# 18_ETH.net
KiCad netlist of a schematic drawn in Altium Designer
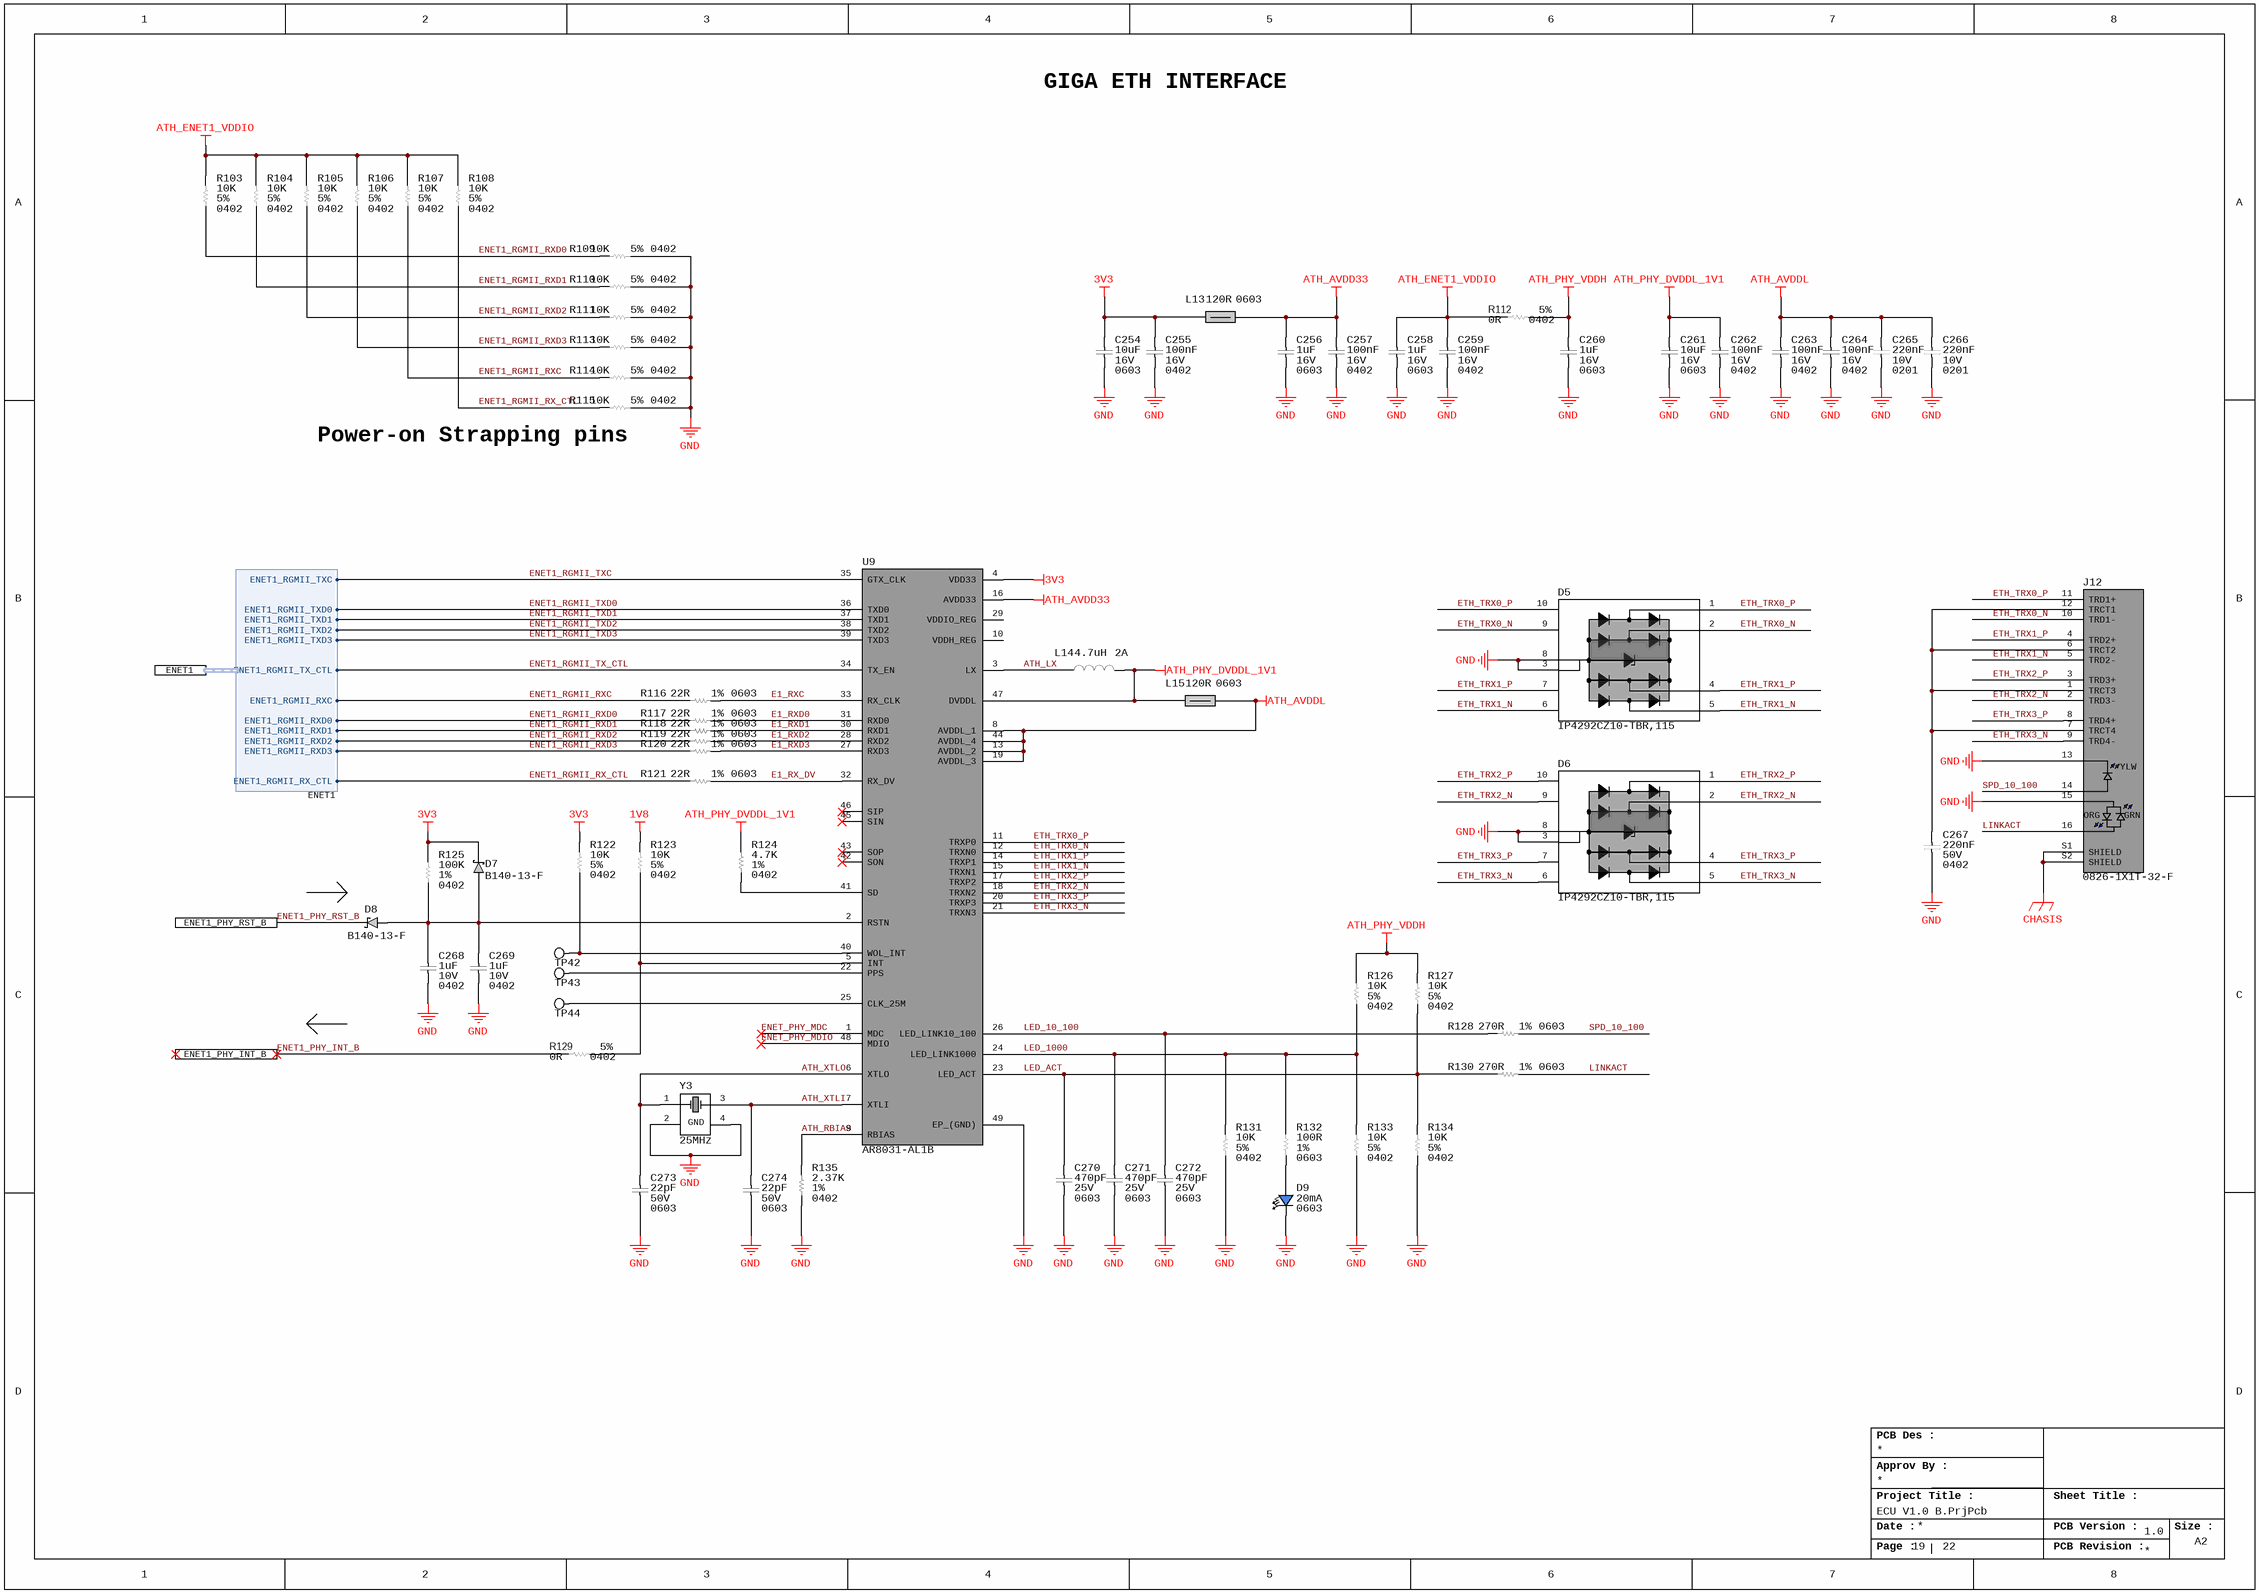
[diagram p0: 18_ETH.SchDoc]

(export (version "E")
  (design (tool "Eeschema 10.0.6"))
  (components
    (comp (ref "C254")
      (value "GRM188R61C106MAALD")
      (footprint "CAP_0603_CAPC1608X08N")
      (description "0603 10 uF 16 V ±20% Tolerance X5R Multilayer Ceramic Chip Capacitor")
      (fields
        (field (name "MANUFACTURER") "Murata")
        (field (name "TOLERANCE") "20%")
        (field (name "VOLTAGE RATING") "16V")
        (field (name "CAPACITANCE") "10uF")
        (field (name "CASE/PACKAGE") "0603")
      )
      (libsource (lib "Electronic Devices_LIB") (part "CAP_10UF_16V_X5R_0603"))
    )
    (comp (ref "C255")
      (value "CL05B104KO5NNNC")
      (footprint "CAP_0402_CAPC1005X05N")
      (description "Multilayer Ceramic Capacitor, 0.1 uF, 16 V, ± 10%, X7R, 0402 [1005 Metric]")
      (fields
        (field (name "MANUFACTURER") "Samsung")
        (field (name "TOLERANCE") "10%")
        (field (name "VOLTAGE RATING") "16V")
        (field (name "CAPACITANCE") "100nF")
        (field (name "CASE/PACKAGE") "0402")
      )
      (libsource (lib "Electronic Devices_LIB") (part "CAP_100NF_16V_X7R_0402"))
    )
    (comp (ref "C256")
      (value "CL10A105KO8NNNC")
      (footprint "CAP_0603_CAPC1608X08N")
      (description "CAP CER 1UF 16V X5R 0603")
      (fields
        (field (name "MANUFACTURER") "Samsung")
        (field (name "TOLERANCE") "10%")
        (field (name "VOLTAGE RATING") "16V")
        (field (name "CAPACITANCE") "1uF")
        (field (name "CASE/PACKAGE") "0603")
      )
      (libsource (lib "Electronic Devices_LIB") (part "CAP_1UF_16V_X5R_0603"))
    )
    (comp (ref "C257")
      (value "CL05B104KO5NNNC")
      (footprint "CAP_0402_CAPC1005X05N")
      (description "Multilayer Ceramic Capacitor, 0.1 uF, 16 V, ± 10%, X7R, 0402 [1005 Metric]")
      (fields
        (field (name "MANUFACTURER") "Samsung")
        (field (name "TOLERANCE") "10%")
        (field (name "VOLTAGE RATING") "16V")
        (field (name "CAPACITANCE") "100nF")
        (field (name "CASE/PACKAGE") "0402")
      )
      (libsource (lib "Electronic Devices_LIB") (part "CAP_100NF_16V_X7R_0402"))
    )
    (comp (ref "C258")
      (value "CL10A105KO8NNNC")
      (footprint "CAP_0603_CAPC1608X08N")
      (description "CAP CER 1UF 16V X5R 0603")
      (fields
        (field (name "MANUFACTURER") "Samsung")
        (field (name "TOLERANCE") "10%")
        (field (name "VOLTAGE RATING") "16V")
        (field (name "CAPACITANCE") "1uF")
        (field (name "CASE/PACKAGE") "0603")
      )
      (libsource (lib "Electronic Devices_LIB") (part "CAP_1UF_16V_X5R_0603"))
    )
    (comp (ref "C259")
      (value "CL05B104KO5NNNC")
      (footprint "CAP_0402_CAPC1005X05N")
      (description "Multilayer Ceramic Capacitor, 0.1 uF, 16 V, ± 10%, X7R, 0402 [1005 Metric]")
      (fields
        (field (name "MANUFACTURER") "Samsung")
        (field (name "TOLERANCE") "10%")
        (field (name "VOLTAGE RATING") "16V")
        (field (name "CAPACITANCE") "100nF")
        (field (name "CASE/PACKAGE") "0402")
      )
      (libsource (lib "Electronic Devices_LIB") (part "CAP_100NF_16V_X7R_0402"))
    )
    (comp (ref "C260")
      (value "CL10A105KO8NNNC")
      (footprint "CAP_0603_CAPC1608X08N")
      (description "CAP CER 1UF 16V X5R 0603")
      (fields
        (field (name "MANUFACTURER") "Samsung")
        (field (name "TOLERANCE") "10%")
        (field (name "VOLTAGE RATING") "16V")
        (field (name "CAPACITANCE") "1uF")
        (field (name "CASE/PACKAGE") "0603")
      )
      (libsource (lib "Electronic Devices_LIB") (part "CAP_1UF_16V_X5R_0603"))
    )
    (comp (ref "C261")
      (value "GRM188R61C106MAALD")
      (footprint "CAP_0603_CAPC1608X08N")
      (description "0603 10 uF 16 V ±20% Tolerance X5R Multilayer Ceramic Chip Capacitor")
      (fields
        (field (name "MANUFACTURER") "Murata")
        (field (name "TOLERANCE") "20%")
        (field (name "VOLTAGE RATING") "16V")
        (field (name "CAPACITANCE") "10uF")
        (field (name "CASE/PACKAGE") "0603")
      )
      (libsource (lib "Electronic Devices_LIB") (part "CAP_10UF_16V_X5R_0603"))
    )
    (comp (ref "C262")
      (value "CL05B104KO5NNNC")
      (footprint "CAP_0402_CAPC1005X05N")
      (description "Multilayer Ceramic Capacitor, 0.1 uF, 16 V, ± 10%, X7R, 0402 [1005 Metric]")
      (fields
        (field (name "MANUFACTURER") "Samsung")
        (field (name "TOLERANCE") "10%")
        (field (name "VOLTAGE RATING") "16V")
        (field (name "CAPACITANCE") "100nF")
        (field (name "CASE/PACKAGE") "0402")
      )
      (libsource (lib "Electronic Devices_LIB") (part "CAP_100NF_16V_X7R_0402"))
    )
    (comp (ref "C263")
      (value "CL05B104KO5NNNC")
      (footprint "CAP_0402_CAPC1005X05N")
      (description "Multilayer Ceramic Capacitor, 0.1 uF, 16 V, ± 10%, X7R, 0402 [1005 Metric]")
      (fields
        (field (name "MANUFACTURER") "Samsung")
        (field (name "TOLERANCE") "10%")
        (field (name "VOLTAGE RATING") "16V")
        (field (name "CAPACITANCE") "100nF")
        (field (name "CASE/PACKAGE") "0402")
      )
      (libsource (lib "Electronic Devices_LIB") (part "CAP_100NF_16V_X7R_0402"))
    )
    (comp (ref "C264")
      (value "CL05B104KO5NNNC")
      (footprint "CAP_0402_CAPC1005X05N")
      (description "Multilayer Ceramic Capacitor, 0.1 uF, 16 V, ± 10%, X7R, 0402 [1005 Metric]")
      (fields
        (field (name "MANUFACTURER") "Samsung")
        (field (name "TOLERANCE") "10%")
        (field (name "VOLTAGE RATING") "16V")
        (field (name "CAPACITANCE") "100nF")
        (field (name "CASE/PACKAGE") "0402")
      )
      (libsource (lib "Electronic Devices_LIB") (part "CAP_100NF_16V_X7R_0402"))
    )
    (comp (ref "C265")
      (value "LMK063BJ224MP-F")
      (footprint "CAP_0201_CAPC0603X03N")
      (description "Multilayer Ceramic Capacitors (High dielectric type), 10V, 0.22 uF, ± 20 %, 0201, X5R, RoHS")
      (fields
        (field (name "MANUFACTURER") "Taiyo Yuden")
        (field (name "TOLERANCE") "20%")
        (field (name "VOLTAGE RATING (DC)") "10V")
        (field (name "CAPACITANCE") "220nF")
        (field (name "CASE/PACKAGE") "0201")
      )
      (libsource (lib "Electronic Devices_LIB") (part "CAP_0.22UF_10V_X5R_0201"))
    )
    (comp (ref "C266")
      (value "LMK063BJ224MP-F")
      (footprint "CAP_0201_CAPC0603X03N")
      (description "Multilayer Ceramic Capacitors (High dielectric type), 10V, 0.22 uF, ± 20 %, 0201, X5R, RoHS")
      (fields
        (field (name "MANUFACTURER") "Taiyo Yuden")
        (field (name "TOLERANCE") "20%")
        (field (name "VOLTAGE RATING (DC)") "10V")
        (field (name "CAPACITANCE") "220nF")
        (field (name "CASE/PACKAGE") "0201")
      )
      (libsource (lib "Electronic Devices_LIB") (part "CAP_0.22UF_10V_X5R_0201"))
    )
    (comp (ref "C267")
      (value "GRM155R61H224KE01W")
      (footprint "CAP_0402_CAPC1005X05N")
      (description "Multilayer Ceramic Capacitor, 0.22 uF, 50 VDC, ± 10%, X5R, 0402 [1005 Metric]")
      (fields
        (field (name "MANUFACTURER") "Murata")
        (field (name "CASE/PACKAGE") "0402")
        (field (name "VOLTAGE RATING (DC)") "50V")
        (field (name "CAPACITANCE") "220nF")
      )
      (libsource (lib "Electronic Devices_LIB") (part "CAP_0.22UF_50V_X5R_0402"))
    )
    (comp (ref "C268")
      (value "GRM155C81A105KA12D")
      (footprint "CAP_0402_CAPC1005X05N")
      (description "0402 10 V 1 uF ±10% Tolerance X6S Multilayer Ceramic Capacitor")
      (fields
        (field (name "MANUFACTURER") "Murata")
        (field (name "TOLERANCE") "10%")
        (field (name "VOLTAGE RATING") "10V")
        (field (name "CAPACITANCE") "1uF")
        (field (name "CASE/PACKAGE") "0402")
      )
      (libsource (lib "Electronic Devices_LIB") (part "CAP_1UF_10V_X6S_0402"))
    )
    (comp (ref "C269")
      (value "GRM155C81A105KA12D")
      (footprint "CAP_0402_CAPC1005X05N")
      (description "0402 10 V 1 uF ±10% Tolerance X6S Multilayer Ceramic Capacitor")
      (fields
        (field (name "MANUFACTURER") "Murata")
        (field (name "TOLERANCE") "10%")
        (field (name "VOLTAGE RATING") "10V")
        (field (name "CAPACITANCE") "1uF")
        (field (name "CASE/PACKAGE") "0402")
      )
      (libsource (lib "Electronic Devices_LIB") (part "CAP_1UF_10V_X6S_0402"))
    )
    (comp (ref "C270")
      (value "C0603C471K3RACTU")
      (footprint "CAP_0603_CAPC1608X08N")
      (fields
        (field (name "MANUFACTURER") "KEMET")
        (field (name "TOLERANCE") "10%")
        (field (name "VOLTAGE RATING") "25V")
        (field (name "CAPACITANCE") "470pF")
        (field (name "CASE CODE (IMPERIAL)") "0603")
      )
      (libsource (lib "Electronic Devices_LIB") (part "CAP_470pF_25V_X7R_0603"))
    )
    (comp (ref "C271")
      (value "C0603C471K3RACTU")
      (footprint "CAP_0603_CAPC1608X08N")
      (fields
        (field (name "MANUFACTURER") "KEMET")
        (field (name "TOLERANCE") "10%")
        (field (name "VOLTAGE RATING") "25V")
        (field (name "CAPACITANCE") "470pF")
        (field (name "CASE CODE (IMPERIAL)") "0603")
      )
      (libsource (lib "Electronic Devices_LIB") (part "CAP_470pF_25V_X7R_0603"))
    )
    (comp (ref "C272")
      (value "C0603C471K3RACTU")
      (footprint "CAP_0603_CAPC1608X08N")
      (fields
        (field (name "MANUFACTURER") "KEMET")
        (field (name "TOLERANCE") "10%")
        (field (name "VOLTAGE RATING") "25V")
        (field (name "CAPACITANCE") "470pF")
        (field (name "CASE CODE (IMPERIAL)") "0603")
      )
      (libsource (lib "Electronic Devices_LIB") (part "CAP_470pF_25V_X7R_0603"))
    )
    (comp (ref "C273")
      (value "C0603C220J5GACTU")
      (footprint "CAP_0603_CAPC1608X08N")
      (description "Multilayer Ceramic Capacitor, 22 pF, 50 V, ï¿½ 5%, C0G (NP0), 0603 [1608 Metric]")
      (fields
        (field (name "MANUFACTURER") "KEMET")
        (field (name "TOLERANCE") "5%")
        (field (name "VOLTAGE RATING (DC)") "50V")
        (field (name "CAPACITANCE") "22pF")
        (field (name "CASE/PACKAGE") "0603")
      )
      (libsource (lib "Electronic Devices_LIB") (part "CAP_22pF_50V_NP0_0603"))
    )
    (comp (ref "C274")
      (value "C0603C220J5GACTU")
      (footprint "CAP_0603_CAPC1608X08N")
      (description "Multilayer Ceramic Capacitor, 22 pF, 50 V, ï¿½ 5%, C0G (NP0), 0603 [1608 Metric]")
      (fields
        (field (name "MANUFACTURER") "KEMET")
        (field (name "TOLERANCE") "5%")
        (field (name "VOLTAGE RATING (DC)") "50V")
        (field (name "CAPACITANCE") "22pF")
        (field (name "CASE/PACKAGE") "0603")
      )
      (libsource (lib "Electronic Devices_LIB") (part "CAP_22pF_50V_NP0_0603"))
    )
    (comp (ref "D5")
      (value "IP4292CZ10-TBR,115")
      (footprint "DIO_TVS_SON50P100X250X50-10N")
      (description "IP4292CZ10 Series 4 Channel 4 V 0.55 pF ESD Protected TVS Diode - DFN2510A-10")
      (fields (field (name "MANUFACTURER") "Nexperia"))
      (libsource (lib "Electronic Devices_LIB") (part "DIO_TVS_4CH_4V_IP4292CZ10-TBR,115"))
    )
    (comp (ref "D6")
      (value "IP4292CZ10-TBR,115")
      (footprint "DIO_TVS_SON50P100X250X50-10N")
      (description "IP4292CZ10 Series 4 Channel 4 V 0.55 pF ESD Protected TVS Diode - DFN2510A-10")
      (fields (field (name "MANUFACTURER") "Nexperia"))
      (libsource (lib "Electronic Devices_LIB") (part "DIO_TVS_4CH_4V_IP4292CZ10-TBR,115"))
    )
    (comp (ref "D7")
      (value "B140-13-F")
      (footprint "DIOM5226X240N")
      (description "Rectifier Diode, Schottky, 1 Phase, 1 Element, 1A, 40V V(RRM), Silicon, DO-214AC")
      (fields (field (name "MANUFACTURER") "Diodes"))
      (libsource (lib "Electronic Devices_LIB") (part "DIO_SCTKY_40V_1A_B140-13-F"))
    )
    (comp (ref "D8")
      (value "B140-13-F")
      (footprint "DIOM5226X240N")
      (description "Rectifier Diode, Schottky, 1 Phase, 1 Element, 1A, 40V V(RRM), Silicon, DO-214AC")
      (fields (field (name "MANUFACTURER") "Diodes"))
      (libsource (lib "Electronic Devices_LIB") (part "DIO_SCTKY_40V_1A_B140-13-F"))
    )
    (comp (ref "D9")
      (value "ASCKCB00-NS3T4010302")
      (footprint "LED_0603-BLUE-0.75mm")
      (description "LED Single Chip Blue 467nm 20mA 2-Pin DFN T/R")
      (fields
        (field (name "MANUFACTURER") "Broadcom")
        (field (name "CASE/PACKCAGE") "0603")
        (field (name "TEST CURRENT") "20mA")
      )
      (libsource (lib "Electronic Devices_LIB") (part "LED_DIO_BLUE_20mA_0603_ASCKCB00-NS3T4010302"))
    )
    (comp (ref "J12")
      (value "0826-1X1T-32-F")
      (footprint "BEL_0826-1X1T-32-F")
      (description "Modular Connectors / Ethernet Connectors RJ45 Connector")
      (fields (field (name "MANUFACTURER") "Bel"))
      (libsource (lib "Electronic Devices_LIB") (part "CONN_RJ45_0826-1X1T-32-F"))
    )
    (comp (ref "L13")
      (value "BLM18PG121SH1D")
      (footprint "IND_0603_INDC1608X08N")
      (description "Ferrite Beads Multi-Layer 120Ohm 25% 100MHz 2A 50mOhm DCR 0603 Automotive Paper T/R")
      (fields
        (field (name "MANUFACTURER") "Murata")
        (field (name "TOLERANCE") "25%")
        (field (name "IMPEDANCE") "120R")
        (field (name "CASE/PACKAGE") "0603")
      )
      (libsource (lib "Electronic Devices_LIB") (part "IND_FERRITE_BEADS_120R_2A_0603_BLM18PG121SH1D"))
    )
    (comp (ref "L14")
      (value "DFE252012P-4R7M=P2")
      (footprint "DFE2HCAH1R0MJ0L")
      (description "Inductor Power Shielded Wirewound 4.7uH 20% 1MHz Metal 1.4A 0.2Ohm DCR 1008 T/R")
      (fields
        (field (name "MANUFACTURER") "Murata")
        (field (name "TOLERANCE") "20%")
        (field (name "CURRENT RATING") "2A")
        (field (name "INDUCTANCE") "4.7uH")
      )
      (libsource (lib "Electronic Devices_LIB") (part "IND_4.7uF_1.4A-DFE252012P-4R7M=P2"))
    )
    (comp (ref "L15")
      (value "BLM18PG121SH1D")
      (footprint "IND_0603_INDC1608X08N")
      (description "Ferrite Beads Multi-Layer 120Ohm 25% 100MHz 2A 50mOhm DCR 0603 Automotive Paper T/R")
      (fields
        (field (name "MANUFACTURER") "Murata")
        (field (name "TOLERANCE") "25%")
        (field (name "IMPEDANCE") "120R")
        (field (name "CASE/PACKAGE") "0603")
      )
      (libsource (lib "Electronic Devices_LIB") (part "IND_FERRITE_BEADS_120R_2A_0603_BLM18PG121SH1D"))
    )
    (comp (ref "R103")
      (value "ERJ-2GEJ103X")
      (footprint "RES_0402_RESC1005X04N")
      (description "Res Thick Film 0402 10K Ohm 5% 1/10W ±200ppm/°C Molded SMD Punched Carrier T/R")
      (fields
        (field (name "MANUFACTURER") "Panasonic")
        (field (name "TOLERANCE") "5%")
        (field (name "RESISTANCE") "10K")
        (field (name "CASE/PACKAGE") "0402")
      )
      (libsource (lib "Electronic Devices_LIB") (part "RES_10K_5%_100mW_0402"))
    )
    (comp (ref "R104")
      (value "ERJ-2GEJ103X")
      (footprint "RES_0402_RESC1005X04N")
      (description "Res Thick Film 0402 10K Ohm 5% 1/10W ±200ppm/°C Molded SMD Punched Carrier T/R")
      (fields
        (field (name "MANUFACTURER") "Panasonic")
        (field (name "TOLERANCE") "5%")
        (field (name "RESISTANCE") "10K")
        (field (name "CASE/PACKAGE") "0402")
      )
      (libsource (lib "Electronic Devices_LIB") (part "RES_10K_5%_100mW_0402"))
    )
    (comp (ref "R105")
      (value "ERJ-2GEJ103X")
      (footprint "RES_0402_RESC1005X04N")
      (description "Res Thick Film 0402 10K Ohm 5% 1/10W ±200ppm/°C Molded SMD Punched Carrier T/R")
      (fields
        (field (name "MANUFACTURER") "Panasonic")
        (field (name "TOLERANCE") "5%")
        (field (name "RESISTANCE") "10K")
        (field (name "CASE/PACKAGE") "0402")
      )
      (libsource (lib "Electronic Devices_LIB") (part "RES_10K_5%_100mW_0402"))
    )
    (comp (ref "R106")
      (value "ERJ-2GEJ103X")
      (footprint "RES_0402_RESC1005X04N")
      (description "Res Thick Film 0402 10K Ohm 5% 1/10W ±200ppm/°C Molded SMD Punched Carrier T/R")
      (fields
        (field (name "MANUFACTURER") "Panasonic")
        (field (name "TOLERANCE") "5%")
        (field (name "RESISTANCE") "10K")
        (field (name "CASE/PACKAGE") "0402")
      )
      (libsource (lib "Electronic Devices_LIB") (part "RES_10K_5%_100mW_0402"))
    )
    (comp (ref "R107")
      (value "ERJ-2GEJ103X")
      (footprint "RES_0402_RESC1005X04N")
      (description "Res Thick Film 0402 10K Ohm 5% 1/10W ±200ppm/°C Molded SMD Punched Carrier T/R")
      (fields
        (field (name "MANUFACTURER") "Panasonic")
        (field (name "TOLERANCE") "5%")
        (field (name "RESISTANCE") "10K")
        (field (name "CASE/PACKAGE") "0402")
      )
      (libsource (lib "Electronic Devices_LIB") (part "RES_10K_5%_100mW_0402"))
    )
    (comp (ref "R108")
      (value "ERJ-2GEJ103X")
      (footprint "RES_0402_RESC1005X04N")
      (description "Res Thick Film 0402 10K Ohm 5% 1/10W ±200ppm/°C Molded SMD Punched Carrier T/R")
      (fields
        (field (name "MANUFACTURER") "Panasonic")
        (field (name "TOLERANCE") "5%")
        (field (name "RESISTANCE") "10K")
        (field (name "CASE/PACKAGE") "0402")
      )
      (libsource (lib "Electronic Devices_LIB") (part "RES_10K_5%_100mW_0402"))
    )
    (comp (ref "R109")
      (value "ERJ-2GEJ103X")
      (footprint "RES_0402_RESC1005X04N")
      (description "Res Thick Film 0402 10K Ohm 5% 1/10W ±200ppm/°C Molded SMD Punched Carrier T/R")
      (fields
        (field (name "MANUFACTURER") "Panasonic")
        (field (name "TOLERANCE") "5%")
        (field (name "RESISTANCE") "10K")
        (field (name "CASE/PACKAGE") "0402")
      )
      (libsource (lib "Electronic Devices_LIB") (part "RES_10K_5%_100mW_0402"))
    )
    (comp (ref "R110")
      (value "ERJ-2GEJ103X")
      (footprint "RES_0402_RESC1005X04N")
      (description "Res Thick Film 0402 10K Ohm 5% 1/10W ±200ppm/°C Molded SMD Punched Carrier T/R")
      (fields
        (field (name "MANUFACTURER") "Panasonic")
        (field (name "TOLERANCE") "5%")
        (field (name "RESISTANCE") "10K")
        (field (name "CASE/PACKAGE") "0402")
      )
      (libsource (lib "Electronic Devices_LIB") (part "RES_10K_5%_100mW_0402"))
    )
    (comp (ref "R111")
      (value "ERJ-2GEJ103X")
      (footprint "RES_0402_RESC1005X04N")
      (description "Res Thick Film 0402 10K Ohm 5% 1/10W ±200ppm/°C Molded SMD Punched Carrier T/R")
      (fields
        (field (name "MANUFACTURER") "Panasonic")
        (field (name "TOLERANCE") "5%")
        (field (name "RESISTANCE") "10K")
        (field (name "CASE/PACKAGE") "0402")
      )
      (libsource (lib "Electronic Devices_LIB") (part "RES_10K_5%_100mW_0402"))
    )
    (comp (ref "R112")
      (value "ERJ-2GE0R00X")
      (footprint "RES_0402_RESC1005X04N")
      (description "SMD Chip Resistor, Jumper, 0 ohm, 100 mW, 0402 [1005 Metric], Thick Film, General Purpose")
      (fields
        (field (name "MANUFACTURER") "Panasonic")
        (field (name "CASE CODE (IMPERIAL)") "0402")
        (field (name "TOLERANCE") "5%")
        (field (name "RESISTANCE") "0R")
      )
      (libsource (lib "Electronic Devices_LIB") (part "RES_0R_5%_100mW_0402"))
    )
    (comp (ref "R113")
      (value "ERJ-2GEJ103X")
      (footprint "RES_0402_RESC1005X04N")
      (description "Res Thick Film 0402 10K Ohm 5% 1/10W ±200ppm/°C Molded SMD Punched Carrier T/R")
      (fields
        (field (name "MANUFACTURER") "Panasonic")
        (field (name "TOLERANCE") "5%")
        (field (name "RESISTANCE") "10K")
        (field (name "CASE/PACKAGE") "0402")
      )
      (libsource (lib "Electronic Devices_LIB") (part "RES_10K_5%_100mW_0402"))
    )
    (comp (ref "R114")
      (value "ERJ-2GEJ103X")
      (footprint "RES_0402_RESC1005X04N")
      (description "Res Thick Film 0402 10K Ohm 5% 1/10W ±200ppm/°C Molded SMD Punched Carrier T/R")
      (fields
        (field (name "MANUFACTURER") "Panasonic")
        (field (name "TOLERANCE") "5%")
        (field (name "RESISTANCE") "10K")
        (field (name "CASE/PACKAGE") "0402")
      )
      (libsource (lib "Electronic Devices_LIB") (part "RES_10K_5%_100mW_0402"))
    )
    (comp (ref "R115")
      (value "ERJ-2GEJ103X")
      (footprint "RES_0402_RESC1005X04N")
      (description "Res Thick Film 0402 10K Ohm 5% 1/10W ±200ppm/°C Molded SMD Punched Carrier T/R")
      (fields
        (field (name "MANUFACTURER") "Panasonic")
        (field (name "TOLERANCE") "5%")
        (field (name "RESISTANCE") "10K")
        (field (name "CASE/PACKAGE") "0402")
      )
      (libsource (lib "Electronic Devices_LIB") (part "RES_10K_5%_100mW_0402"))
    )
    (comp (ref "R116")
      (value "RC0603FR-0722RL")
      (footprint "RES_0603_RESC1608X04N")
      (description "Res Thick Film 0603 22 Ohm 1% 0.1W(1/10W) ±100ppm/C Pad SMD T/R")
      (fields
        (field (name "MANUFACTURER") "Yageo")
        (field (name "TOLERANCE") "1%")
        (field (name "RESISTANCE") "22R")
        (field (name "CASE/PACKAGE") "0603")
      )
      (libsource (lib "Electronic Devices_LIB") (part "RES_22R_1%_100mW_0603"))
    )
    (comp (ref "R117")
      (value "RC0603FR-0722RL")
      (footprint "RES_0603_RESC1608X04N")
      (description "Res Thick Film 0603 22 Ohm 1% 0.1W(1/10W) ±100ppm/C Pad SMD T/R")
      (fields
        (field (name "MANUFACTURER") "Yageo")
        (field (name "TOLERANCE") "1%")
        (field (name "RESISTANCE") "22R")
        (field (name "CASE/PACKAGE") "0603")
      )
      (libsource (lib "Electronic Devices_LIB") (part "RES_22R_1%_100mW_0603"))
    )
    (comp (ref "R118")
      (value "RC0603FR-0722RL")
      (footprint "RES_0603_RESC1608X04N")
      (description "Res Thick Film 0603 22 Ohm 1% 0.1W(1/10W) ±100ppm/C Pad SMD T/R")
      (fields
        (field (name "MANUFACTURER") "Yageo")
        (field (name "TOLERANCE") "1%")
        (field (name "RESISTANCE") "22R")
        (field (name "CASE/PACKAGE") "0603")
      )
      (libsource (lib "Electronic Devices_LIB") (part "RES_22R_1%_100mW_0603"))
    )
    (comp (ref "R119")
      (value "RC0603FR-0722RL")
      (footprint "RES_0603_RESC1608X04N")
      (description "Res Thick Film 0603 22 Ohm 1% 0.1W(1/10W) ±100ppm/C Pad SMD T/R")
      (fields
        (field (name "MANUFACTURER") "Yageo")
        (field (name "TOLERANCE") "1%")
        (field (name "RESISTANCE") "22R")
        (field (name "CASE/PACKAGE") "0603")
      )
      (libsource (lib "Electronic Devices_LIB") (part "RES_22R_1%_100mW_0603"))
    )
    (comp (ref "R120")
      (value "RC0603FR-0722RL")
      (footprint "RES_0603_RESC1608X04N")
      (description "Res Thick Film 0603 22 Ohm 1% 0.1W(1/10W) ±100ppm/C Pad SMD T/R")
      (fields
        (field (name "MANUFACTURER") "Yageo")
        (field (name "TOLERANCE") "1%")
        (field (name "RESISTANCE") "22R")
        (field (name "CASE/PACKAGE") "0603")
      )
      (libsource (lib "Electronic Devices_LIB") (part "RES_22R_1%_100mW_0603"))
    )
    (comp (ref "R121")
      (value "RC0603FR-0722RL")
      (footprint "RES_0603_RESC1608X04N")
      (description "Res Thick Film 0603 22 Ohm 1% 0.1W(1/10W) ±100ppm/C Pad SMD T/R")
      (fields
        (field (name "MANUFACTURER") "Yageo")
        (field (name "TOLERANCE") "1%")
        (field (name "RESISTANCE") "22R")
        (field (name "CASE/PACKAGE") "0603")
      )
      (libsource (lib "Electronic Devices_LIB") (part "RES_22R_1%_100mW_0603"))
    )
    (comp (ref "R122")
      (value "ERJ-2GEJ103X")
      (footprint "RES_0402_RESC1005X04N")
      (description "Res Thick Film 0402 10K Ohm 5% 1/10W ±200ppm/°C Molded SMD Punched Carrier T/R")
      (fields
        (field (name "MANUFACTURER") "Panasonic")
        (field (name "TOLERANCE") "5%")
        (field (name "RESISTANCE") "10K")
        (field (name "CASE/PACKAGE") "0402")
      )
      (libsource (lib "Electronic Devices_LIB") (part "RES_10K_5%_100mW_0402"))
    )
    (comp (ref "R123")
      (value "ERJ-2GEJ103X")
      (footprint "RES_0402_RESC1005X04N")
      (description "Res Thick Film 0402 10K Ohm 5% 1/10W ±200ppm/°C Molded SMD Punched Carrier T/R")
      (fields
        (field (name "MANUFACTURER") "Panasonic")
        (field (name "TOLERANCE") "5%")
        (field (name "RESISTANCE") "10K")
        (field (name "CASE/PACKAGE") "0402")
      )
      (libsource (lib "Electronic Devices_LIB") (part "RES_10K_5%_100mW_0402"))
    )
    (comp (ref "R124")
      (value "ERJ-2RKF4701X")
      (footprint "RES_0402_RESC1005X04N")
      (description "Res Thick Film 0402 4.7K Ohm 1% 0.1W ±100ppm/°C Molded SMD Punched Carrier T/R")
      (fields
        (field (name "MANUFACTURER") "Panasonic")
        (field (name "TOLERANCE") "1%")
        (field (name "CASE CODE (IMPERIAL)") "0402")
        (field (name "RESISTANCE") "4.7K")
      )
      (libsource (lib "Electronic Devices_LIB") (part "RES_4.7K_1%_100mW_0402"))
    )
    (comp (ref "R125")
      (value "RC0402FR-07100KL")
      (footprint "RES_0402_RESC1005X04N")
      (description "SMD Chip Resistor, 100 kOhm, ± 1%, 63 mW, 0402 [1005 Metric], Thick Film, General Purpose")
      (fields
        (field (name "MANUFACTURER") "Yageo")
        (field (name "RESISTANCE") "100K")
        (field (name "TOLERANCE") "1%")
        (field (name "CASE/PACKAGE") "0402")
      )
      (libsource (lib "Electronic Devices_LIB") (part "RES_100K_1%_100mW_0402"))
    )
    (comp (ref "R126")
      (value "ERJ-2GEJ103X")
      (footprint "RES_0402_RESC1005X04N")
      (description "Res Thick Film 0402 10K Ohm 5% 1/10W ±200ppm/°C Molded SMD Punched Carrier T/R")
      (fields
        (field (name "MANUFACTURER") "Panasonic")
        (field (name "TOLERANCE") "5%")
        (field (name "RESISTANCE") "10K")
        (field (name "CASE/PACKAGE") "0402")
      )
      (libsource (lib "Electronic Devices_LIB") (part "RES_10K_5%_100mW_0402"))
    )
    (comp (ref "R127")
      (value "ERJ-2GEJ103X")
      (footprint "RES_0402_RESC1005X04N")
      (description "Res Thick Film 0402 10K Ohm 5% 1/10W ±200ppm/°C Molded SMD Punched Carrier T/R")
      (fields
        (field (name "MANUFACTURER") "Panasonic")
        (field (name "TOLERANCE") "5%")
        (field (name "RESISTANCE") "10K")
        (field (name "CASE/PACKAGE") "0402")
      )
      (libsource (lib "Electronic Devices_LIB") (part "RES_10K_5%_100mW_0402"))
    )
    (comp (ref "R128")
      (value "RC0603FR-07270RL")
      (footprint "RES_0603_RESC1608X04N")
      (description "SMD Chip Resistor, 270 Ohm, ï¿½ 1%, 100 mW, 0603 [1608 Metric], Thick Film, General Purpose")
      (fields
        (field (name "MANUFACTURER") "Yageo")
        (field (name "TOLERANCE") "1%")
        (field (name "RESISTANCE") "270R")
        (field (name "CASE/PACKAGE") "0603")
      )
      (libsource (lib "Electronic Devices_LIB") (part "RES_270R_1%_100mW_0603"))
    )
    (comp (ref "R129")
      (value "ERJ-2GE0R00X")
      (footprint "RES_0402_RESC1005X04N")
      (description "SMD Chip Resistor, Jumper, 0 ohm, 100 mW, 0402 [1005 Metric], Thick Film, General Purpose")
      (fields
        (field (name "MANUFACTURER") "Panasonic")
        (field (name "CASE CODE (IMPERIAL)") "0402")
        (field (name "TOLERANCE") "5%")
        (field (name "RESISTANCE") "0R")
      )
      (libsource (lib "Electronic Devices_LIB") (part "RES_0R_5%_100mW_0402"))
    )
    (comp (ref "R130")
      (value "RC0603FR-07270RL")
      (footprint "RES_0603_RESC1608X04N")
      (description "SMD Chip Resistor, 270 Ohm, ï¿½ 1%, 100 mW, 0603 [1608 Metric], Thick Film, General Purpose")
      (fields
        (field (name "MANUFACTURER") "Yageo")
        (field (name "TOLERANCE") "1%")
        (field (name "RESISTANCE") "270R")
        (field (name "CASE/PACKAGE") "0603")
      )
      (libsource (lib "Electronic Devices_LIB") (part "RES_270R_1%_100mW_0603"))
    )
    (comp (ref "R131")
      (value "ERJ-2GEJ103X")
      (footprint "RES_0402_RESC1005X04N")
      (description "Res Thick Film 0402 10K Ohm 5% 1/10W ±200ppm/°C Molded SMD Punched Carrier T/R")
      (fields
        (field (name "MANUFACTURER") "Panasonic")
        (field (name "TOLERANCE") "5%")
        (field (name "RESISTANCE") "10K")
        (field (name "CASE/PACKAGE") "0402")
      )
      (libsource (lib "Electronic Devices_LIB") (part "RES_10K_5%_100mW_0402"))
    )
    (comp (ref "R132")
      (value "ERJ3EKF1000V")
      (footprint "CAP_0603_CAPC1608X08N")
      (description "Res Thick Film 0603 100 Ohm 1% 1/10W ±100ppm/°C Molded SMD Punched Carrier T/R")
      (fields
        (field (name "MANUFACTURER") "Panasonic")
        (field (name "CASE CODE (IMPERIAL)") "0603")
        (field (name "TOLERANCE") "1%")
        (field (name "RESISTANCE") "100R")
      )
      (libsource (lib "Electronic Devices_LIB") (part "RES_100R_1%_100MW_0603"))
    )
    (comp (ref "R133")
      (value "ERJ-2GEJ103X")
      (footprint "RES_0402_RESC1005X04N")
      (description "Res Thick Film 0402 10K Ohm 5% 1/10W ±200ppm/°C Molded SMD Punched Carrier T/R")
      (fields
        (field (name "MANUFACTURER") "Panasonic")
        (field (name "TOLERANCE") "5%")
        (field (name "RESISTANCE") "10K")
        (field (name "CASE/PACKAGE") "0402")
      )
      (libsource (lib "Electronic Devices_LIB") (part "RES_10K_5%_100mW_0402"))
    )
    (comp (ref "R134")
      (value "ERJ-2GEJ103X")
      (footprint "RES_0402_RESC1005X04N")
      (description "Res Thick Film 0402 10K Ohm 5% 1/10W ±200ppm/°C Molded SMD Punched Carrier T/R")
      (fields
        (field (name "MANUFACTURER") "Panasonic")
        (field (name "TOLERANCE") "5%")
        (field (name "RESISTANCE") "10K")
        (field (name "CASE/PACKAGE") "0402")
      )
      (libsource (lib "Electronic Devices_LIB") (part "RES_10K_5%_100mW_0402"))
    )
    (comp (ref "R135")
      (value "ERJ-2RKF2371X")
      (footprint "RES_0402_RESC1005X04N")
      (description "Res Thick Film 0402 2.37K Ohm 1% 1/10W ±100ppm/°C Molded SMD Punched Carrier T/R")
      (fields
        (field (name "MANUFACTURER") "Panasonic")
        (field (name "TOLERANCE") "1%")
        (field (name "RESISTANCE") "2.37K")
        (field (name "CASE/PACKAGE") "0402")
      )
      (libsource (lib "Electronic Devices_LIB") (part "RES_2.37K_1%_100mW_0402"))
    )
    (comp (ref "TP42")
      (value "NO COMPONENT")
      (footprint "TP_PAD_0.5MM_SMD_ROUND")
      (description "Test Point, SMD pad, round, 1.5mm, 1.6mm, 3mm diameter")
      (libsource (lib "Electronic Devices_LIB") (part "TP_PAD_SMD_SMALL"))
    )
    (comp (ref "TP43")
      (value "NO COMPONENT")
      (footprint "TP_PAD_0.5MM_SMD_ROUND")
      (description "Test Point, SMD pad, round, 1.5mm, 1.6mm, 3mm diameter")
      (libsource (lib "Electronic Devices_LIB") (part "TP_PAD_SMD_SMALL"))
    )
    (comp (ref "TP44")
      (value "NO COMPONENT")
      (footprint "TP_PAD_0.5MM_SMD_ROUND")
      (description "Test Point, SMD pad, round, 1.5mm, 1.6mm, 3mm diameter")
      (libsource (lib "Electronic Devices_LIB") (part "TP_PAD_SMD_SMALL"))
    )
    (comp (ref "U9")
      (value "AR8031-AL1B")
      (footprint "QFN40P600X600X80-49N")
      (description "IC TRANSCEIVER ETHERNET 48-QFN / PHY 10Mbps/100Mbps/1Gbps 3.3V 48-Pin QFN EP Tray")
      (fields (field (name "MANUFACTURER") "Qualcomm"))
      (libsource (lib "Electronic Devices_LIB") (part "IC_TRANSCEIVER_ETH_AR8031-AL1B"))
    )
    (comp (ref "Y3")
      (value "405C35B25M00000")
      (footprint "405C35B25M00000")
      (description "405 Series 25 MHz ±30 ppm 13 pF -20 to +70 °C Surface Mount Quartz Crystal")
      (fields
        (field (name "MANUFACTURER") "CTS")
        (field (name "FREQUENCY") "25MHz")
        (field (name "TOLERANCE") "30ppm")
      )
      (libsource (lib "Electronic Devices_LIB") (part "CRYSTAL_25MHZ_13PF_405C35B25M00000"))
    )
  )
  (nets
    (net (code "2") (name "/ATH_LX") (class "Default")
      (node (ref "L14") (pin "1") (pinfunction "1_1") (pintype "passive"))
      (node (ref "U9") (pin "3") (pinfunction "LX_3") (pintype "passive"))
    )
    (net (code "3") (name "/ATH_RBIAS") (class "Default")
      (node (ref "R135") (pin "2") (pinfunction "2_2") (pintype "passive"))
      (node (ref "U9") (pin "9") (pinfunction "RBIAS_9") (pintype "passive"))
    )
    (net (code "4") (name "/ATH_XTLI") (class "Default")
      (node (ref "C274") (pin "2") (pinfunction "2_2") (pintype "passive"))
      (node (ref "U9") (pin "7") (pinfunction "XTLI_7") (pintype "passive"))
      (node (ref "Y3") (pin "3") (pinfunction "XTAL_2_3") (pintype "passive"))
    )
    (net (code "5") (name "/ATH_XTLO") (class "Default")
      (node (ref "C273") (pin "2") (pinfunction "2_2") (pintype "passive"))
      (node (ref "U9") (pin "6") (pinfunction "XTLO_6") (pintype "passive"))
      (node (ref "Y3") (pin "1") (pinfunction "XTAL_1_1") (pintype "passive"))
    )
    (net (code "6") (name "/E1_RXC") (class "Default")
      (node (ref "R116") (pin "2") (pinfunction "2_2") (pintype "passive"))
      (node (ref "U9") (pin "33") (pinfunction "RX_CLK_33") (pintype "passive"))
    )
    (net (code "7") (name "/E1_RXD0") (class "Default")
      (node (ref "R117") (pin "2") (pinfunction "2_2") (pintype "passive"))
      (node (ref "U9") (pin "31") (pinfunction "RXD0_31") (pintype "passive"))
    )
    (net (code "8") (name "/E1_RXD1") (class "Default")
      (node (ref "R118") (pin "2") (pinfunction "2_2") (pintype "passive"))
      (node (ref "U9") (pin "30") (pinfunction "RXD1_30") (pintype "passive"))
    )
    (net (code "9") (name "/E1_RXD2") (class "Default")
      (node (ref "R119") (pin "2") (pinfunction "2_2") (pintype "passive"))
      (node (ref "U9") (pin "28") (pinfunction "RXD2_28") (pintype "passive"))
    )
    (net (code "10") (name "/E1_RXD3") (class "Default")
      (node (ref "R120") (pin "2") (pinfunction "2_2") (pintype "passive"))
      (node (ref "U9") (pin "27") (pinfunction "RXD3_27") (pintype "passive"))
    )
    (net (code "11") (name "/E1_RX_DV") (class "Default")
      (node (ref "R121") (pin "2") (pinfunction "2_2") (pintype "passive"))
      (node (ref "U9") (pin "32") (pinfunction "RX_DV_32") (pintype "passive"))
    )
    (net (code "12") (name "/ENET1_PHY_INT_B") (class "Default")
      (node (ref "R129") (pin "1") (pinfunction "1_1") (pintype "passive+no_connect"))
    )
    (net (code "13") (name "/ENET1_PHY_RST_B") (class "Default")
      (node (ref "D8") (pin "1") (pinfunction "K_1") (pintype "passive"))
    )
    (net (code "14") (name "/ENET1_RGMII_RXC") (class "Default")
      (node (ref "R107") (pin "1") (pinfunction "1_1") (pintype "passive"))
      (node (ref "R114") (pin "2") (pinfunction "2_2") (pintype "passive"))
      (node (ref "R116") (pin "1") (pinfunction "1_1") (pintype "passive"))
    )
    (net (code "15") (name "/ENET1_RGMII_RXD0") (class "Default")
      (node (ref "R103") (pin "1") (pinfunction "1_1") (pintype "passive"))
      (node (ref "R109") (pin "2") (pinfunction "2_2") (pintype "passive"))
      (node (ref "R117") (pin "1") (pinfunction "1_1") (pintype "passive"))
    )
    (net (code "16") (name "/ENET1_RGMII_RXD1") (class "Default")
      (node (ref "R104") (pin "1") (pinfunction "1_1") (pintype "passive"))
      (node (ref "R110") (pin "2") (pinfunction "2_2") (pintype "passive"))
      (node (ref "R118") (pin "1") (pinfunction "1_1") (pintype "passive"))
    )
    (net (code "17") (name "/ENET1_RGMII_RXD2") (class "Default")
      (node (ref "R105") (pin "1") (pinfunction "1_1") (pintype "passive"))
      (node (ref "R111") (pin "2") (pinfunction "2_2") (pintype "passive"))
      (node (ref "R119") (pin "1") (pinfunction "1_1") (pintype "passive"))
    )
    (net (code "18") (name "/ENET1_RGMII_RXD3") (class "Default")
      (node (ref "R106") (pin "1") (pinfunction "1_1") (pintype "passive"))
      (node (ref "R113") (pin "2") (pinfunction "2_2") (pintype "passive"))
      (node (ref "R120") (pin "1") (pinfunction "1_1") (pintype "passive"))
    )
    (net (code "19") (name "/ENET1_RGMII_RX_CTL") (class "Default")
      (node (ref "R108") (pin "1") (pinfunction "1_1") (pintype "passive"))
      (node (ref "R115") (pin "2") (pinfunction "2_2") (pintype "passive"))
      (node (ref "R121") (pin "1") (pinfunction "1_1") (pintype "passive"))
    )
    (net (code "20") (name "/ENET1_RGMII_TXC") (class "Default")
      (node (ref "U9") (pin "35") (pinfunction "GTX_CLK_35") (pintype "passive"))
    )
    (net (code "21") (name "/ENET1_RGMII_TXD0") (class "Default")
      (node (ref "U9") (pin "36") (pinfunction "TXD0_36") (pintype "passive"))
    )
    (net (code "22") (name "/ENET1_RGMII_TXD1") (class "Default")
      (node (ref "U9") (pin "37") (pinfunction "TXD1_37") (pintype "passive"))
    )
    (net (code "23") (name "/ENET1_RGMII_TXD2") (class "Default")
      (node (ref "U9") (pin "38") (pinfunction "TXD2_38") (pintype "passive"))
    )
    (net (code "24") (name "/ENET1_RGMII_TXD3") (class "Default")
      (node (ref "U9") (pin "39") (pinfunction "TXD3_39") (pintype "passive"))
    )
    (net (code "25") (name "/ENET1_RGMII_TX_CTL") (class "Default")
      (node (ref "U9") (pin "34") (pinfunction "TX_EN_34") (pintype "passive"))
    )
    (net (code "26") (name "/ENET_PHY_MDC") (class "Default")
      (node (ref "U9") (pin "1") (pinfunction "MDC_1") (pintype "passive+no_connect"))
    )
    (net (code "27") (name "/ENET_PHY_MDIO") (class "Default")
      (node (ref "U9") (pin "48") (pinfunction "MDIO_48") (pintype "passive+no_connect"))
    )
    (net (code "28") (name "/ETH_TRX0_N") (class "Default")
      (node (ref "D5") (pin "2") (pinfunction "CH2_2") (pintype "passive"))
      (node (ref "D5") (pin "9") (pinfunction "NC3_9") (pintype "passive"))
      (node (ref "J12") (pin "10") (pinfunction "TRD1-_10") (pintype "passive"))
      (node (ref "U9") (pin "12") (pinfunction "TRXN0_12") (pintype "passive"))
    )
    (net (code "29") (name "/ETH_TRX0_P") (class "Default")
      (node (ref "D5") (pin "1") (pinfunction "CH1_1") (pintype "passive"))
      (node (ref "D5") (pin "10") (pinfunction "NC4_10") (pintype "passive"))
      (node (ref "J12") (pin "11") (pinfunction "TRD1+_11") (pintype "passive"))
      (node (ref "U9") (pin "11") (pinfunction "TRXP0_11") (pintype "passive"))
    )
    (net (code "30") (name "/ETH_TRX1_N") (class "Default")
      (node (ref "D5") (pin "5") (pinfunction "CH4_5") (pintype "passive"))
      (node (ref "D5") (pin "6") (pinfunction "NC1_6") (pintype "passive"))
      (node (ref "J12") (pin "5") (pinfunction "TRD2-_5") (pintype "passive"))
      (node (ref "U9") (pin "15") (pinfunction "TRXN1_15") (pintype "passive"))
    )
    (net (code "31") (name "/ETH_TRX1_P") (class "Default")
      (node (ref "D5") (pin "4") (pinfunction "CH3_4") (pintype "passive"))
      (node (ref "D5") (pin "7") (pinfunction "NC2_7") (pintype "passive"))
      (node (ref "J12") (pin "4") (pinfunction "TRD2+_4") (pintype "passive"))
      (node (ref "U9") (pin "14") (pinfunction "TRXP1_14") (pintype "passive"))
    )
    (net (code "32") (name "/ETH_TRX2_N") (class "Default")
      (node (ref "D6") (pin "2") (pinfunction "CH2_2") (pintype "passive"))
      (node (ref "D6") (pin "9") (pinfunction "NC3_9") (pintype "passive"))
      (node (ref "J12") (pin "2") (pinfunction "TRD3-_2") (pintype "passive"))
      (node (ref "U9") (pin "18") (pinfunction "TRXN2_18") (pintype "passive"))
    )
    (net (code "33") (name "/ETH_TRX2_P") (class "Default")
      (node (ref "D6") (pin "1") (pinfunction "CH1_1") (pintype "passive"))
      (node (ref "D6") (pin "10") (pinfunction "NC4_10") (pintype "passive"))
      (node (ref "J12") (pin "3") (pinfunction "TRD3+_3") (pintype "passive"))
      (node (ref "U9") (pin "17") (pinfunction "TRXP2_17") (pintype "passive"))
    )
    (net (code "34") (name "/ETH_TRX3_N") (class "Default")
      (node (ref "D6") (pin "5") (pinfunction "CH4_5") (pintype "passive"))
      (node (ref "D6") (pin "6") (pinfunction "NC1_6") (pintype "passive"))
      (node (ref "J12") (pin "9") (pinfunction "TRD4-_9") (pintype "passive"))
      (node (ref "U9") (pin "21") (pinfunction "TRXN3_21") (pintype "passive"))
    )
    (net (code "35") (name "/ETH_TRX3_P") (class "Default")
      (node (ref "D6") (pin "4") (pinfunction "CH3_4") (pintype "passive"))
      (node (ref "D6") (pin "7") (pinfunction "NC2_7") (pintype "passive"))
      (node (ref "J12") (pin "8") (pinfunction "TRD4+_8") (pintype "passive"))
      (node (ref "U9") (pin "20") (pinfunction "TRXP3_20") (pintype "passive"))
    )
    (net (code "36") (name "/LED_10_100") (class "Default")
      (node (ref "C272") (pin "2") (pinfunction "2_2") (pintype "passive"))
      (node (ref "R128") (pin "1") (pinfunction "1_1") (pintype "passive"))
      (node (ref "U9") (pin "26") (pinfunction "LED_LINK10_100_26") (pintype "passive"))
    )
    (net (code "37") (name "/LED_1000") (class "Default")
      (node (ref "C271") (pin "2") (pinfunction "2_2") (pintype "passive"))
      (node (ref "R126") (pin "1") (pinfunction "1_1") (pintype "passive"))
      (node (ref "R131") (pin "2") (pinfunction "2_2") (pintype "passive"))
      (node (ref "R132") (pin "1") (pinfunction "1_1") (pintype "passive"))
      (node (ref "R133") (pin "2") (pinfunction "2_2") (pintype "passive"))
      (node (ref "U9") (pin "24") (pinfunction "LED_LINK1000_24") (pintype "passive"))
    )
    (net (code "38") (name "/LED_ACT") (class "Default")
      (node (ref "C270") (pin "2") (pinfunction "2_2") (pintype "passive"))
      (node (ref "R127") (pin "1") (pinfunction "1_1") (pintype "passive"))
      (node (ref "R130") (pin "1") (pinfunction "1_1") (pintype "passive"))
      (node (ref "R134") (pin "2") (pinfunction "2_2") (pintype "passive"))
      (node (ref "U9") (pin "23") (pinfunction "LED_ACT_23") (pintype "passive"))
    )
    (net (code "39") (name "/LINKACT") (class "Default")
      (node (ref "J12") (pin "16") (pinfunction "16_16") (pintype "passive"))
      (node (ref "R130") (pin "2") (pinfunction "2_2") (pintype "passive"))
    )
    (net (code "40") (name "/SPD_10_100") (class "Default")
      (node (ref "J12") (pin "14") (pinfunction "14_14") (pintype "passive"))
      (node (ref "R128") (pin "2") (pinfunction "2_2") (pintype "passive"))
    )
    (net (code "42") (name "1V8") (class "Default")
      (node (ref "R123") (pin "2") (pinfunction "2_2") (pintype "passive"))
    )
    (net (code "43") (name "3V3") (class "Default")
      (node (ref "C254") (pin "2") (pinfunction "2_2") (pintype "passive"))
      (node (ref "C255") (pin "2") (pinfunction "2_2") (pintype "passive"))
      (node (ref "D7") (pin "1") (pinfunction "K_1") (pintype "passive"))
      (node (ref "L13") (pin "1") (pinfunction "1_1") (pintype "passive"))
      (node (ref "R122") (pin "2") (pinfunction "2_2") (pintype "passive"))
      (node (ref "R125") (pin "2") (pinfunction "2_2") (pintype "passive"))
      (node (ref "U9") (pin "4") (pinfunction "VDD33_4") (pintype "passive"))
    )
    (net (code "44") (name "ATH_AVDD33") (class "Default")
      (node (ref "C256") (pin "2") (pinfunction "2_2") (pintype "passive"))
      (node (ref "C257") (pin "2") (pinfunction "2_2") (pintype "passive"))
      (node (ref "L13") (pin "2") (pinfunction "2_2") (pintype "passive"))
      (node (ref "U9") (pin "16") (pinfunction "AVDD33_16") (pintype "passive"))
    )
    (net (code "45") (name "ATH_AVDDL") (class "Default")
      (node (ref "C263") (pin "2") (pinfunction "2_2") (pintype "passive"))
      (node (ref "C264") (pin "2") (pinfunction "2_2") (pintype "passive"))
      (node (ref "C265") (pin "2") (pinfunction "2_2") (pintype "passive"))
      (node (ref "C266") (pin "2") (pinfunction "2_2") (pintype "passive"))
      (node (ref "L15") (pin "2") (pinfunction "2_2") (pintype "passive"))
      (node (ref "U9") (pin "13") (pinfunction "AVDDL_2_13") (pintype "passive"))
      (node (ref "U9") (pin "19") (pinfunction "AVDDL_3_19") (pintype "passive"))
      (node (ref "U9") (pin "44") (pinfunction "AVDDL_4_44") (pintype "passive"))
      (node (ref "U9") (pin "8") (pinfunction "AVDDL_1_8") (pintype "passive"))
    )
    (net (code "46") (name "ATH_ENET1_VDDIO") (class "Default")
      (node (ref "C258") (pin "2") (pinfunction "2_2") (pintype "passive"))
      (node (ref "C259") (pin "2") (pinfunction "2_2") (pintype "passive"))
      (node (ref "R103") (pin "2") (pinfunction "2_2") (pintype "passive"))
      (node (ref "R104") (pin "2") (pinfunction "2_2") (pintype "passive"))
      (node (ref "R105") (pin "2") (pinfunction "2_2") (pintype "passive"))
      (node (ref "R106") (pin "2") (pinfunction "2_2") (pintype "passive"))
      (node (ref "R107") (pin "2") (pinfunction "2_2") (pintype "passive"))
      (node (ref "R108") (pin "2") (pinfunction "2_2") (pintype "passive"))
      (node (ref "R112") (pin "1") (pinfunction "1_1") (pintype "passive"))
    )
    (net (code "47") (name "ATH_PHY_DVDDL_1V1") (class "Default")
      (node (ref "C261") (pin "2") (pinfunction "2_2") (pintype "passive"))
      (node (ref "C262") (pin "2") (pinfunction "2_2") (pintype "passive"))
      (node (ref "L14") (pin "2") (pinfunction "2_2") (pintype "passive"))
      (node (ref "L15") (pin "1") (pinfunction "1_1") (pintype "passive"))
      (node (ref "R124") (pin "2") (pinfunction "2_2") (pintype "passive"))
      (node (ref "U9") (pin "47") (pinfunction "DVDDL_47") (pintype "passive"))
    )
    (net (code "48") (name "ATH_PHY_VDDH") (class "Default")
      (node (ref "C260") (pin "2") (pinfunction "2_2") (pintype "passive"))
      (node (ref "R112") (pin "2") (pinfunction "2_2") (pintype "passive"))
      (node (ref "R126") (pin "2") (pinfunction "2_2") (pintype "passive"))
      (node (ref "R127") (pin "2") (pinfunction "2_2") (pintype "passive"))
    )
    (net (code "49") (name "CHASIS") (class "Default")
      (node (ref "J12") (pin "S1") (pinfunction "SHIELD_S1") (pintype "passive"))
      (node (ref "J12") (pin "S2") (pinfunction "SHIELD_S2") (pintype "passive"))
    )
    (net (code "50") (name "GND") (class "Default")
      (node (ref "C254") (pin "1") (pinfunction "1_1") (pintype "passive"))
      (node (ref "C255") (pin "1") (pinfunction "1_1") (pintype "passive"))
      (node (ref "C256") (pin "1") (pinfunction "1_1") (pintype "passive"))
      (node (ref "C257") (pin "1") (pinfunction "1_1") (pintype "passive"))
      (node (ref "C258") (pin "1") (pinfunction "1_1") (pintype "passive"))
      (node (ref "C259") (pin "1") (pinfunction "1_1") (pintype "passive"))
      (node (ref "C260") (pin "1") (pinfunction "1_1") (pintype "passive"))
      (node (ref "C261") (pin "1") (pinfunction "1_1") (pintype "passive"))
      (node (ref "C262") (pin "1") (pinfunction "1_1") (pintype "passive"))
      (node (ref "C263") (pin "1") (pinfunction "1_1") (pintype "passive"))
      (node (ref "C264") (pin "1") (pinfunction "1_1") (pintype "passive"))
      (node (ref "C265") (pin "1") (pinfunction "1_1") (pintype "passive"))
      (node (ref "C266") (pin "1") (pinfunction "1_1") (pintype "passive"))
      (node (ref "C267") (pin "1") (pinfunction "1_1") (pintype "passive"))
      (node (ref "C268") (pin "1") (pinfunction "1_1") (pintype "passive"))
      (node (ref "C269") (pin "1") (pinfunction "1_1") (pintype "passive"))
      (node (ref "C270") (pin "1") (pinfunction "1_1") (pintype "passive"))
      (node (ref "C271") (pin "1") (pinfunction "1_1") (pintype "passive"))
      (node (ref "C272") (pin "1") (pinfunction "1_1") (pintype "passive"))
      (node (ref "C273") (pin "1") (pinfunction "1_1") (pintype "passive"))
      (node (ref "C274") (pin "1") (pinfunction "1_1") (pintype "passive"))
      (node (ref "D5") (pin "3") (pinfunction "GND1_3") (pintype "power_in"))
      (node (ref "D5") (pin "8") (pinfunction "GND2_8") (pintype "power_in"))
      (node (ref "D6") (pin "3") (pinfunction "GND1_3") (pintype "power_in"))
      (node (ref "D6") (pin "8") (pinfunction "GND2_8") (pintype "power_in"))
      (node (ref "D9") (pin "1") (pinfunction "C_1") (pintype "passive"))
      (node (ref "J12") (pin "13") (pinfunction "13_13") (pintype "passive"))
      (node (ref "J12") (pin "15") (pinfunction "15_15") (pintype "passive"))
      (node (ref "R109") (pin "1") (pinfunction "1_1") (pintype "passive"))
      (node (ref "R110") (pin "1") (pinfunction "1_1") (pintype "passive"))
      (node (ref "R111") (pin "1") (pinfunction "1_1") (pintype "passive"))
      (node (ref "R113") (pin "1") (pinfunction "1_1") (pintype "passive"))
      (node (ref "R114") (pin "1") (pinfunction "1_1") (pintype "passive"))
      (node (ref "R115") (pin "1") (pinfunction "1_1") (pintype "passive"))
      (node (ref "R131") (pin "1") (pinfunction "1_1") (pintype "passive"))
      (node (ref "R133") (pin "1") (pinfunction "1_1") (pintype "passive"))
      (node (ref "R134") (pin "1") (pinfunction "1_1") (pintype "passive"))
      (node (ref "R135") (pin "1") (pinfunction "1_1") (pintype "passive"))
      (node (ref "U9") (pin "49") (pinfunction "EP_(GND)_49") (pintype "passive"))
      (node (ref "Y3") (pin "2") (pinfunction "GND_1_2") (pintype "passive"))
      (node (ref "Y3") (pin "4") (pinfunction "GND_2_4") (pintype "passive"))
    )
    (net (code "51") (name "Net-(D7-A)") (class "Default")
      (node (ref "C268") (pin "2") (pinfunction "2_2") (pintype "passive"))
      (node (ref "C269") (pin "2") (pinfunction "2_2") (pintype "passive"))
      (node (ref "D7") (pin "2") (pinfunction "A_2") (pintype "passive"))
      (node (ref "D8") (pin "2") (pinfunction "A_2") (pintype "passive"))
      (node (ref "R125") (pin "1") (pinfunction "1_1") (pintype "passive"))
      (node (ref "U9") (pin "2") (pinfunction "RSTN_2") (pintype "passive"))
    )
    (net (code "52") (name "Net-(D9-A)") (class "Default")
      (node (ref "D9") (pin "2") (pinfunction "A_2") (pintype "passive"))
      (node (ref "R132") (pin "2") (pinfunction "2_2") (pintype "passive"))
    )
    (net (code "53") (name "Net-(J12-TRCT1)") (class "Default")
      (node (ref "C267") (pin "2") (pinfunction "2_2") (pintype "passive"))
      (node (ref "J12") (pin "1") (pinfunction "TRCT3_1") (pintype "passive"))
      (node (ref "J12") (pin "12") (pinfunction "TRCT1_12") (pintype "passive"))
      (node (ref "J12") (pin "6") (pinfunction "TRCT2_6") (pintype "passive"))
      (node (ref "J12") (pin "7") (pinfunction "TRCT4_7") (pintype "passive"))
    )
    (net (code "54") (name "Net-(U9-CLK_25M)") (class "Default")
      (node (ref "TP44") (pin "1") (pinfunction "1_1") (pintype "passive"))
      (node (ref "U9") (pin "25") (pinfunction "CLK_25M_25") (pintype "passive"))
    )
    (net (code "55") (name "Net-(U9-INT)") (class "Default")
      (node (ref "R123") (pin "1") (pinfunction "1_1") (pintype "passive"))
      (node (ref "R129") (pin "2") (pinfunction "2_2") (pintype "passive"))
      (node (ref "U9") (pin "5") (pinfunction "INT_5") (pintype "passive"))
    )
    (net (code "56") (name "Net-(U9-PPS)") (class "Default")
      (node (ref "TP43") (pin "1") (pinfunction "1_1") (pintype "passive"))
      (node (ref "U9") (pin "22") (pinfunction "PPS_22") (pintype "passive"))
    )
    (net (code "57") (name "Net-(U9-SD)") (class "Default")
      (node (ref "R124") (pin "1") (pinfunction "1_1") (pintype "passive"))
      (node (ref "U9") (pin "41") (pinfunction "SD_41") (pintype "passive"))
    )
    (net (code "58") (name "Net-(U9-WOL_INT)") (class "Default")
      (node (ref "R122") (pin "1") (pinfunction "1_1") (pintype "passive"))
      (node (ref "TP42") (pin "1") (pinfunction "1_1") (pintype "passive"))
      (node (ref "U9") (pin "40") (pinfunction "WOL_INT_40") (pintype "passive"))
    )
    (net (code "59") (name "unconnected-(U9-SIN-Pad45)") (class "Default")
      (node (ref "U9") (pin "45") (pinfunction "SIN_45") (pintype "passive+no_connect"))
    )
    (net (code "60") (name "unconnected-(U9-SIP-Pad46)") (class "Default")
      (node (ref "U9") (pin "46") (pinfunction "SIP_46") (pintype "passive+no_connect"))
    )
    (net (code "61") (name "unconnected-(U9-SON-Pad42)") (class "Default")
      (node (ref "U9") (pin "42") (pinfunction "SON_42") (pintype "passive+no_connect"))
    )
    (net (code "62") (name "unconnected-(U9-SOP-Pad43)") (class "Default")
      (node (ref "U9") (pin "43") (pinfunction "SOP_43") (pintype "passive+no_connect"))
    )
    (net (code "63") (name "unconnected-(U9-VDDH_REG-Pad10)") (class "Default")
      (node (ref "U9") (pin "10") (pinfunction "VDDH_REG_10") (pintype "passive"))
    )
    (net (code "64") (name "unconnected-(U9-VDDIO_REG-Pad29)") (class "Default")
      (node (ref "U9") (pin "29") (pinfunction "VDDIO_REG_29") (pintype "passive"))
    )
  )
)
